# ScanMasterVCI.net
KiCad netlist of a schematic drawn in EAGLE
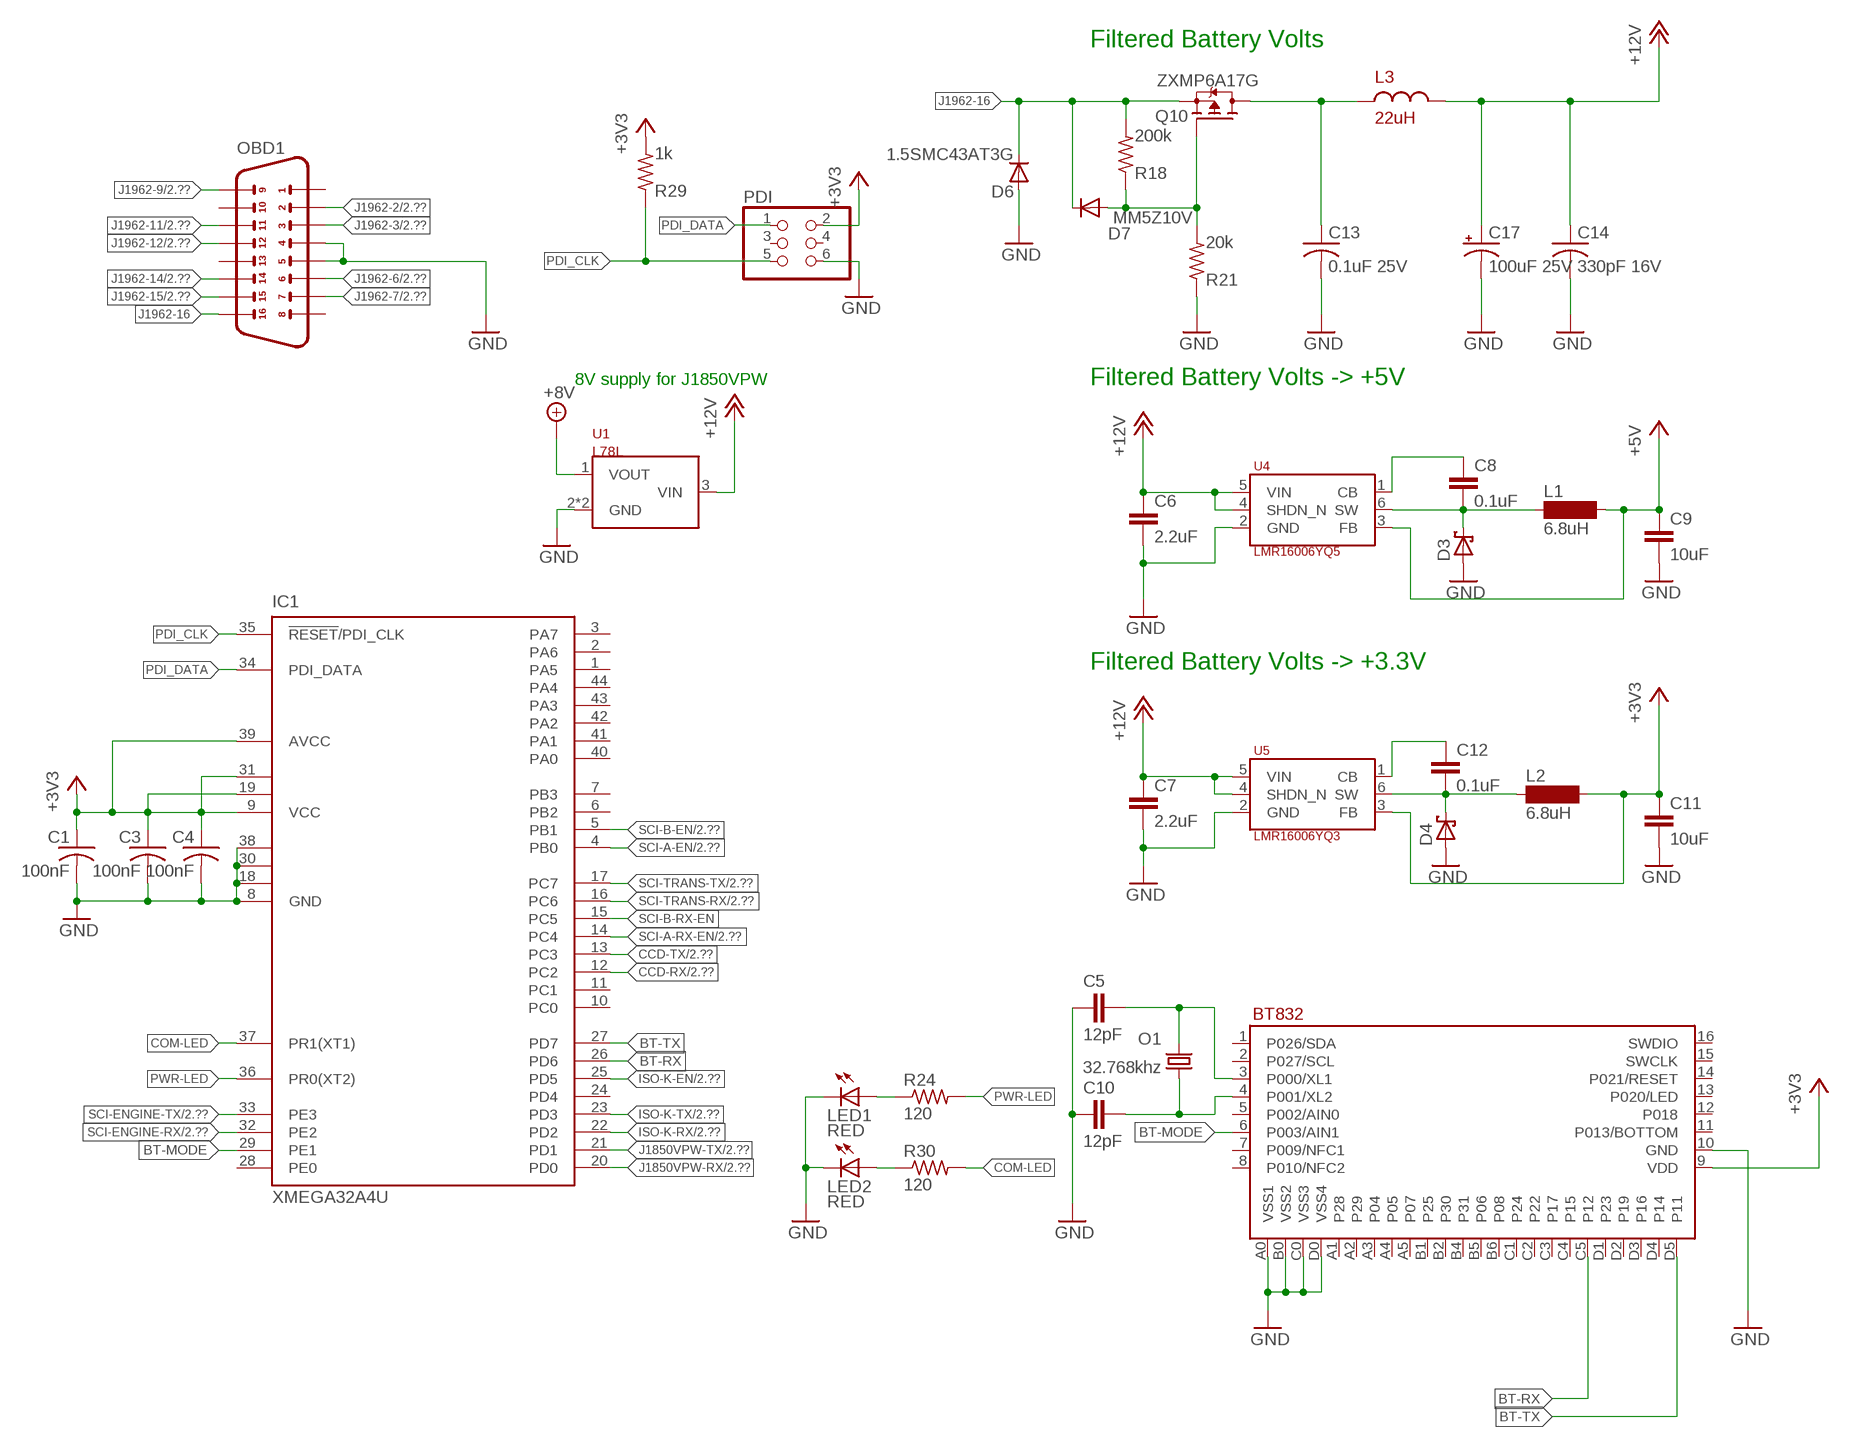
[diagram p0: schematic, sheet 1]
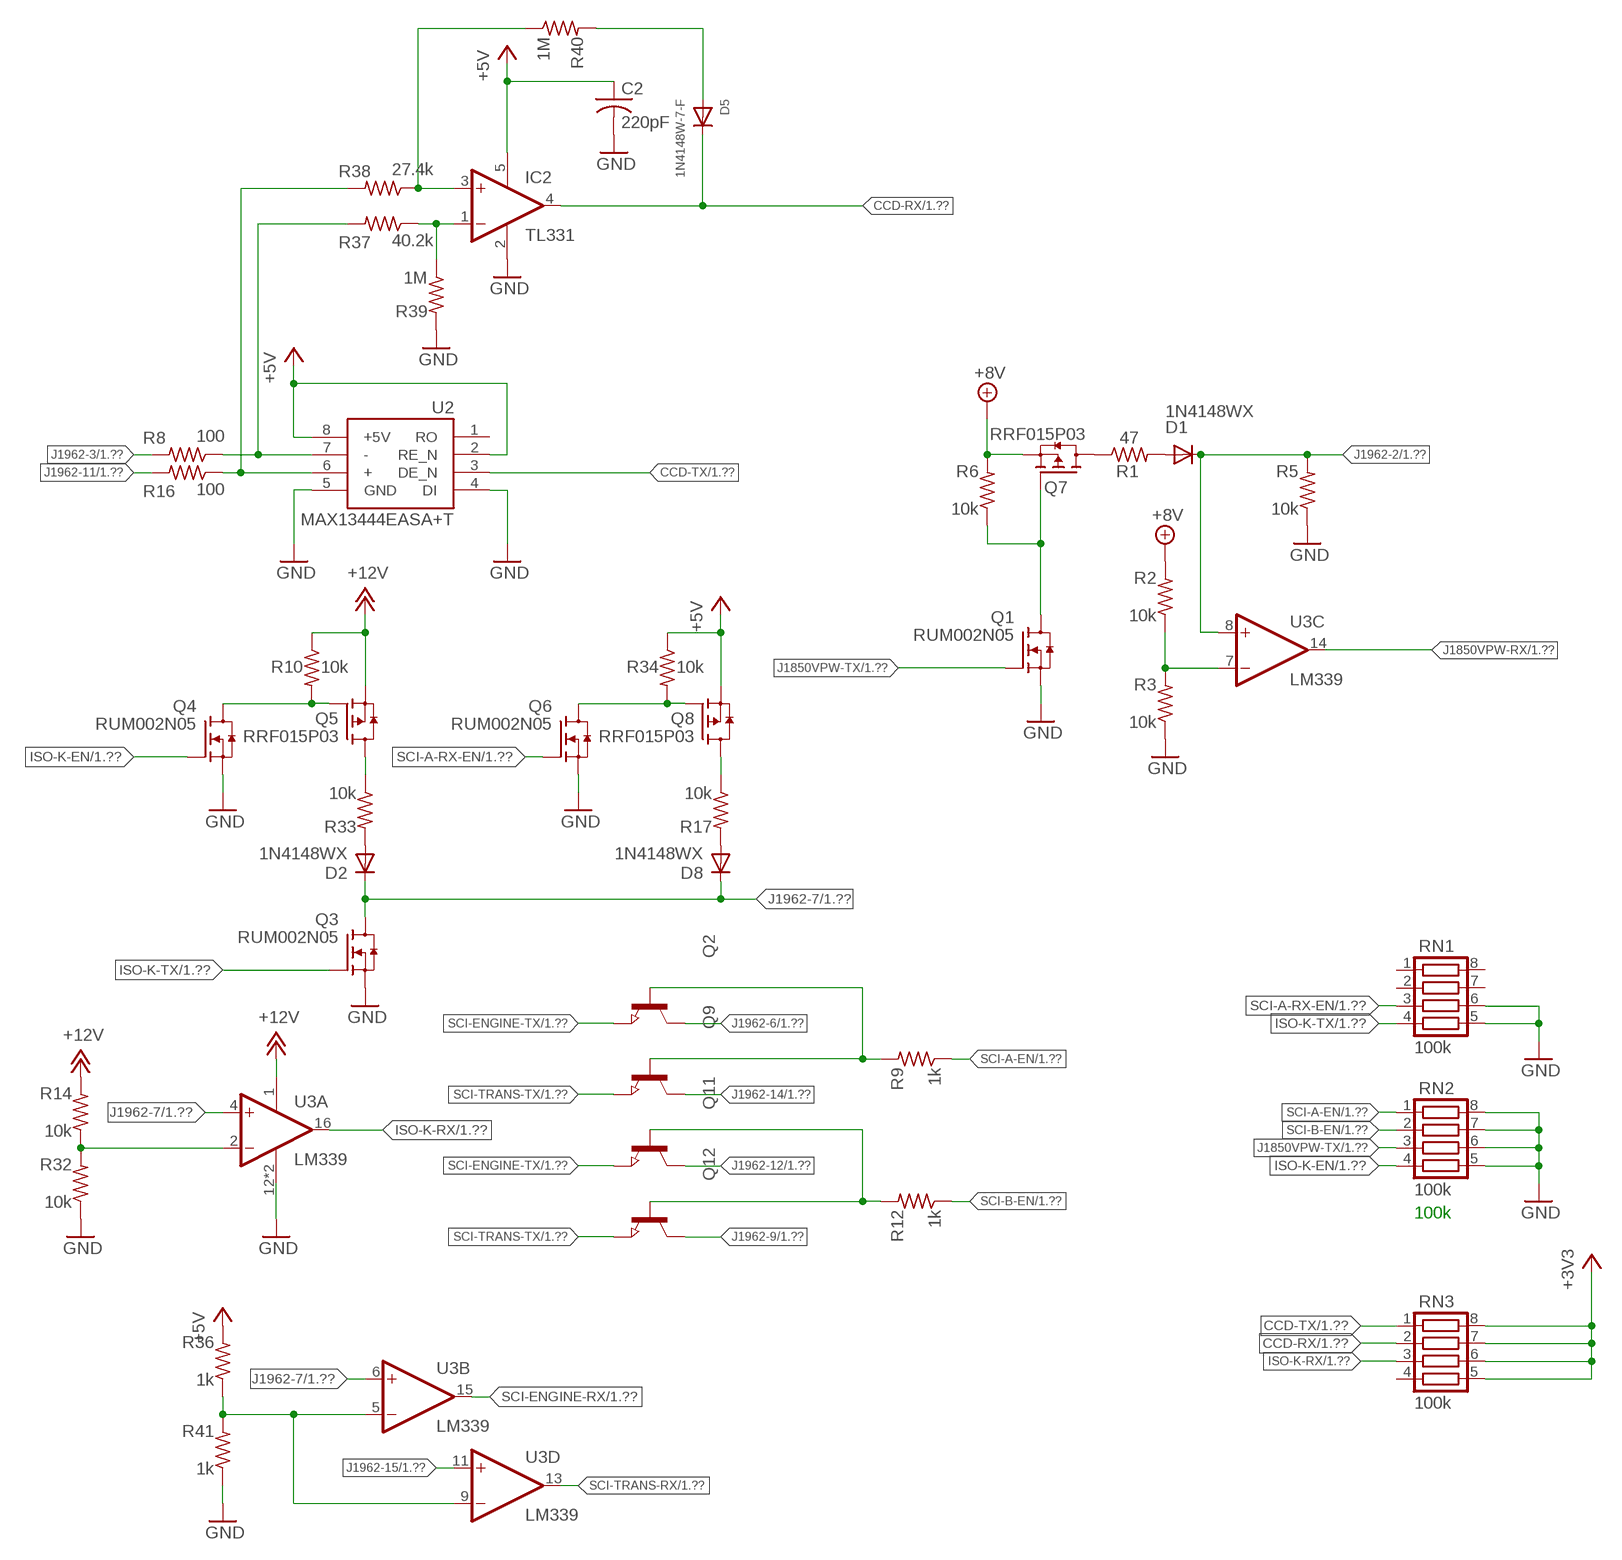
[diagram p1: schematic, sheet 2]

(export (version "E")
  (design (tool "Eeschema 10.0.6"))
  (components
    (comp (ref "C2")
      (value "220pF")
      (footprint "eagle-import:C0603")
      (libsource (lib "eagle-import") (part "C-USC0603"))
    )
    (comp (ref "D1")
      (value "1N4148WX")
      (footprint "eagle-import:SOD323-R")
      (libsource (lib "eagle-import") (part "DIODE-SOD323-R"))
    )
    (comp (ref "D2")
      (value "1N4148WX")
      (footprint "eagle-import:SOD323-R")
      (libsource (lib "eagle-import") (part "DIODE-SOD323-R"))
    )
    (comp (ref "D5")
      (value "1N4148W-7-F")
      (footprint "eagle-import:SOD123FL")
      (libsource (lib "eagle-import") (part "1N4148W-7-F"))
    )
    (comp (ref "D8")
      (value "1N4148WX")
      (footprint "eagle-import:SOD323-R")
      (libsource (lib "eagle-import") (part "DIODE-SOD323-R"))
    )
    (comp (ref "IC2")
      (value "TL331")
      (footprint "eagle-import:DBV-R-PDSO-G5")
      (libsource (lib "eagle-import") (part "TL331"))
    )
    (comp (ref "Q1")
      (value "RUM002N05")
      (footprint "eagle-import:EMT3")
      (libsource (lib "eagle-import") (part "RUM002N05"))
    )
    (comp (ref "Q2")
      (value "NPN-TRANSISTOR_SOT23")
      (footprint "eagle-import:SOT23")
      (libsource (lib "eagle-import") (part "NPN-TRANSISTOR_SOT23"))
    )
    (comp (ref "Q3")
      (value "RUM002N05")
      (footprint "eagle-import:EMT3")
      (libsource (lib "eagle-import") (part "RUM002N05"))
    )
    (comp (ref "Q4")
      (value "RUM002N05")
      (footprint "eagle-import:EMT3")
      (libsource (lib "eagle-import") (part "RUM002N05"))
    )
    (comp (ref "Q5")
      (value "RRF015P03")
      (footprint "eagle-import:SOT323")
      (libsource (lib "eagle-import") (part "RRF015P03"))
    )
    (comp (ref "Q6")
      (value "RUM002N05")
      (footprint "eagle-import:EMT3")
      (libsource (lib "eagle-import") (part "RUM002N05"))
    )
    (comp (ref "Q7")
      (value "RRF015P03")
      (footprint "eagle-import:SOT323")
      (libsource (lib "eagle-import") (part "RRF015P03"))
    )
    (comp (ref "Q8")
      (value "RRF015P03")
      (footprint "eagle-import:SOT323")
      (libsource (lib "eagle-import") (part "RRF015P03"))
    )
    (comp (ref "Q9")
      (value "NPN-TRANSISTOR_SOT23")
      (footprint "eagle-import:SOT23")
      (libsource (lib "eagle-import") (part "NPN-TRANSISTOR_SOT23"))
    )
    (comp (ref "Q11")
      (value "NPN-TRANSISTOR_SOT23")
      (footprint "eagle-import:SOT23")
      (libsource (lib "eagle-import") (part "NPN-TRANSISTOR_SOT23"))
    )
    (comp (ref "Q12")
      (value "NPN-TRANSISTOR_SOT23")
      (footprint "eagle-import:SOT23")
      (libsource (lib "eagle-import") (part "NPN-TRANSISTOR_SOT23"))
    )
    (comp (ref "R1")
      (value "47")
      (footprint "eagle-import:R0603")
      (libsource (lib "eagle-import") (part "R-US_R0603"))
    )
    (comp (ref "R2")
      (value "10k")
      (footprint "eagle-import:R0603")
      (libsource (lib "eagle-import") (part "R-US_R0603"))
    )
    (comp (ref "R3")
      (value "10k")
      (footprint "eagle-import:R0603")
      (libsource (lib "eagle-import") (part "R-US_R0603"))
    )
    (comp (ref "R5")
      (value "10k")
      (footprint "eagle-import:R0603")
      (libsource (lib "eagle-import") (part "R-US_R0603"))
    )
    (comp (ref "R6")
      (value "10k")
      (footprint "eagle-import:R0603")
      (libsource (lib "eagle-import") (part "R-US_R0603"))
    )
    (comp (ref "R8")
      (value "100")
      (footprint "eagle-import:R0603")
      (libsource (lib "eagle-import") (part "R-US_R0603"))
    )
    (comp (ref "R9")
      (value "1k")
      (footprint "eagle-import:R0603")
      (libsource (lib "eagle-import") (part "R-US_R0603"))
    )
    (comp (ref "R10")
      (value "10k")
      (footprint "eagle-import:R0603")
      (libsource (lib "eagle-import") (part "R-US_R0603"))
    )
    (comp (ref "R12")
      (value "1k")
      (footprint "eagle-import:R0603")
      (libsource (lib "eagle-import") (part "R-US_R0603"))
    )
    (comp (ref "R14")
      (value "10k")
      (footprint "eagle-import:R0603")
      (libsource (lib "eagle-import") (part "R-US_R0603"))
    )
    (comp (ref "R16")
      (value "100")
      (footprint "eagle-import:R0603")
      (libsource (lib "eagle-import") (part "R-US_R0603"))
    )
    (comp (ref "R17")
      (value "10k")
      (footprint "eagle-import:R0603")
      (libsource (lib "eagle-import") (part "R-US_R0603"))
    )
    (comp (ref "R32")
      (value "10k")
      (footprint "eagle-import:R0603")
      (libsource (lib "eagle-import") (part "R-US_R0603"))
    )
    (comp (ref "R33")
      (value "10k")
      (footprint "eagle-import:R0603")
      (libsource (lib "eagle-import") (part "R-US_R0603"))
    )
    (comp (ref "R34")
      (value "10k")
      (footprint "eagle-import:R0603")
      (libsource (lib "eagle-import") (part "R-US_R0603"))
    )
    (comp (ref "R36")
      (value "1k")
      (footprint "eagle-import:R0603")
      (libsource (lib "eagle-import") (part "R-US_R0603"))
    )
    (comp (ref "R37")
      (value "40.2k")
      (footprint "eagle-import:R0603")
      (libsource (lib "eagle-import") (part "R-US_R0603"))
    )
    (comp (ref "R38")
      (value "27.4k")
      (footprint "eagle-import:R0603")
      (libsource (lib "eagle-import") (part "R-US_R0603"))
    )
    (comp (ref "R39")
      (value "1M")
      (footprint "eagle-import:R0603")
      (libsource (lib "eagle-import") (part "R-US_R0603"))
    )
    (comp (ref "R40")
      (value "1M")
      (footprint "eagle-import:R0603")
      (libsource (lib "eagle-import") (part "R-US_R0603"))
    )
    (comp (ref "R41")
      (value "1k")
      (footprint "eagle-import:R0603")
      (libsource (lib "eagle-import") (part "R-US_R0603"))
    )
    (comp (ref "RN1")
      (value "100k")
      (footprint "eagle-import:CTS742C083")
      (libsource (lib "eagle-import") (part "CTS742C083"))
    )
    (comp (ref "RN2")
      (value "100k")
      (footprint "eagle-import:CTS742C083")
      (libsource (lib "eagle-import") (part "CTS742C083"))
    )
    (comp (ref "RN3")
      (value "100k")
      (footprint "eagle-import:CTS742C083")
      (libsource (lib "eagle-import") (part "CTS742C083"))
    )
    (comp (ref "U2")
      (value "MAX13444EASA+T")
      (footprint "eagle-import:SO08")
      (libsource (lib "eagle-import") (part "MAX13444EASA+SMD"))
    )
    (comp (ref "U3")
      (value "LM339")
      (footprint "eagle-import:QFN16")
      (libsource (lib "eagle-import") (part "LM339"))
    )
    (comp (ref "C1")
      (value "100nF")
      (footprint "eagle-import:C0402")
      (libsource (lib "eagle-import") (part "C-USC0402"))
    )
    (comp (ref "C3")
      (value "100nF")
      (footprint "eagle-import:C0402")
      (libsource (lib "eagle-import") (part "C-USC0402"))
    )
    (comp (ref "C4")
      (value "100nF")
      (footprint "eagle-import:C0402")
      (libsource (lib "eagle-import") (part "C-USC0402"))
    )
    (comp (ref "C5")
      (value "12pF")
      (footprint "eagle-import:0603")
      (libsource (lib "eagle-import") (part "12PF-0603-50V-5%"))
    )
    (comp (ref "C6")
      (value "2.2uF")
      (footprint "eagle-import:1206")
      (libsource (lib "eagle-import") (part "2.2UF-1206-50V-10%"))
    )
    (comp (ref "C7")
      (value "2.2uF")
      (footprint "eagle-import:1206")
      (libsource (lib "eagle-import") (part "2.2UF-1206-50V-10%"))
    )
    (comp (ref "C8")
      (value "0.1uF")
      (footprint "eagle-import:0603")
      (libsource (lib "eagle-import") (part "0.1UF-0603-25V-(+80/-20%)"))
    )
    (comp (ref "C9")
      (value "10uF")
      (footprint "eagle-import:0603")
      (libsource (lib "eagle-import") (part "10UF-0603-6.3V-20%"))
    )
    (comp (ref "C10")
      (value "12pF")
      (footprint "eagle-import:0603")
      (libsource (lib "eagle-import") (part "12PF-0603-50V-5%"))
    )
    (comp (ref "C11")
      (value "10uF")
      (footprint "eagle-import:0603")
      (libsource (lib "eagle-import") (part "10UF-0603-6.3V-20%"))
    )
    (comp (ref "C12")
      (value "0.1uF")
      (footprint "eagle-import:0603")
      (libsource (lib "eagle-import") (part "0.1UF-0603-25V-(+80/-20%)"))
    )
    (comp (ref "C13")
      (value "0.1uF 25V")
      (footprint "eagle-import:C0603")
      (libsource (lib "eagle-import") (part "C-USC0603"))
    )
    (comp (ref "C14")
      (value "330pF 16V")
      (footprint "eagle-import:C0603")
      (libsource (lib "eagle-import") (part "C-USC0603"))
    )
    (comp (ref "C17")
      (value "100uF 25V")
      (footprint "eagle-import:CPOL-RADIAL-2.5MM-6.5MM")
      (libsource (lib "eagle-import") (part "100UF-POLAR-RADIAL-2.5MM-25V-20%"))
    )
    (comp (ref "D3")
      (value "SM5817PL")
      (footprint "eagle-import:SOD123FL")
      (libsource (lib "eagle-import") (part "SM5817PL"))
    )
    (comp (ref "D4")
      (value "SM5817PL")
      (footprint "eagle-import:SOD123FL")
      (libsource (lib "eagle-import") (part "SM5817PL"))
    )
    (comp (ref "D6")
      (value "1.5SMC43AT3G")
      (footprint "eagle-import:SMC")
      (libsource (lib "eagle-import") (part "DIODE-SMC"))
    )
    (comp (ref "D7")
      (value "MM5Z10V")
      (footprint "eagle-import:SOD523")
      (libsource (lib "eagle-import") (part "DIODE-SOD523"))
    )
    (comp (ref "IC1")
      (value "XMEGA32A4U")
      (footprint "eagle-import:MLF44-TH")
      (libsource (lib "eagle-import") (part "XMEGA16A4M1"))
    )
    (comp (ref "L1")
      (value "6.8uH")
      (footprint "eagle-import:SM-1206")
      (libsource (lib "eagle-import") (part "SM-1206"))
    )
    (comp (ref "L2")
      (value "6.8uH")
      (footprint "eagle-import:SM-1206")
      (libsource (lib "eagle-import") (part "SM-1206"))
    )
    (comp (ref "L3")
      (value "22uH")
      (footprint "eagle-import:L0603")
      (libsource (lib "eagle-import") (part "INDUCTOR"))
    )
    (comp (ref "LED1")
      (value "RED")
      (footprint "eagle-import:CHIP-LED0603")
      (libsource (lib "eagle-import") (part "LEDCHIP-LED0603"))
    )
    (comp (ref "LED2")
      (value "RED")
      (footprint "eagle-import:CHIP-LED0603")
      (libsource (lib "eagle-import") (part "LEDCHIP-LED0603"))
    )
    (comp (ref "O1")
      (value "32.768khz")
      (footprint "eagle-import:FC-135")
      (libsource (lib "eagle-import") (part "SER4103"))
    )
    (comp (ref "OBD1")
      (value "OBD2_OBD2_90")
      (footprint "eagle-import:OBD2")
      (libsource (lib "eagle-import") (part "OBD2_OBD2_90"))
    )
    (comp (ref "PDI")
      (value "PINHD-2X3")
      (footprint "eagle-import:2X03")
      (libsource (lib "eagle-import") (part "PINHD-2X3"))
    )
    (comp (ref "Q10")
      (value "ZXMP6A17G")
      (footprint "eagle-import:SOT223")
      (libsource (lib "eagle-import") (part "ZXMP6A17G"))
    )
    (comp (ref "R18")
      (value "200k")
      (footprint "eagle-import:R0603")
      (libsource (lib "eagle-import") (part "R-US_R0603"))
    )
    (comp (ref "R21")
      (value "20k")
      (footprint "eagle-import:R0603")
      (libsource (lib "eagle-import") (part "R-US_R0603"))
    )
    (comp (ref "R24")
      (value "120")
      (footprint "eagle-import:R0603")
      (libsource (lib "eagle-import") (part "resistor_348_R-US_R0603"))
    )
    (comp (ref "R29")
      (value "1k")
      (footprint "eagle-import:R0603")
      (libsource (lib "eagle-import") (part "R-US_R0603"))
    )
    (comp (ref "R30")
      (value "120")
      (footprint "eagle-import:R0603")
      (libsource (lib "eagle-import") (part "resistor_348_R-US_R0603"))
    )
    (comp (ref "U1")
      (value "L78L")
      (footprint "eagle-import:SOT89")
      (libsource (lib "eagle-import") (part "L78L"))
    )
    (comp (ref "U4")
      (value "LMR16006YQ5")
      (footprint "eagle-import:SOT6")
      (libsource (lib "eagle-import") (part "LMR16006Y"))
    )
    (comp (ref "U5")
      (value "LMR16006YQ3")
      (footprint "eagle-import:SOT6")
      (libsource (lib "eagle-import") (part "LMR16006Y"))
    )
    (comp (ref "U6")
      (value "BT832A")
      (footprint "eagle-import:BT832A")
      (libsource (lib "eagle-import") (part "BT832A"))
    )
  )
  (nets
    (net (code "1") (name "+3V3") (class "Default")
      (node (ref "C1") (pin "1") (pinfunction "1_1") (pintype "passive"))
      (node (ref "C11") (pin "1") (pinfunction "1_1") (pintype "passive"))
      (node (ref "C3") (pin "1") (pinfunction "1_1") (pintype "passive"))
      (node (ref "C4") (pin "1") (pinfunction "1_1") (pintype "passive"))
      (node (ref "IC1") (pin "19") (pinfunction "VCC1_19") (pintype "power_in"))
      (node (ref "IC1") (pin "31") (pinfunction "VCC2_31") (pintype "power_in"))
      (node (ref "IC1") (pin "39") (pinfunction "AVCC_39") (pintype "power_in"))
      (node (ref "IC1") (pin "9") (pinfunction "VCC_9") (pintype "power_in"))
      (node (ref "L2") (pin "2") (pinfunction "2_2") (pintype "passive"))
      (node (ref "PDI") (pin "2") (pinfunction "2_2") (pintype "passive"))
      (node (ref "R29") (pin "2") (pinfunction "2_2") (pintype "passive"))
      (node (ref "RN3") (pin "5") (pinfunction "5_5") (pintype "passive"))
      (node (ref "RN3") (pin "6") (pinfunction "6_6") (pintype "passive"))
      (node (ref "RN3") (pin "7") (pinfunction "7_7") (pintype "passive"))
      (node (ref "RN3") (pin "8") (pinfunction "8_8") (pintype "passive"))
      (node (ref "U5") (pin "3") (pinfunction "FB_3") (pintype "input"))
      (node (ref "U6") (pin "9") (pinfunction "VDD_9") (pintype "bidirectional"))
    )
    (net (code "2") (name "+5V") (class "Default")
      (node (ref "C2") (pin "1") (pinfunction "1_1") (pintype "passive"))
      (node (ref "C9") (pin "1") (pinfunction "1_1") (pintype "passive"))
      (node (ref "IC2") (pin "5") (pinfunction "V+_5") (pintype "power_in"))
      (node (ref "L1") (pin "2") (pinfunction "2_2") (pintype "passive"))
      (node (ref "Q8") (pin "2") (pinfunction "S_2") (pintype "passive"))
      (node (ref "R34") (pin "1") (pinfunction "1_1") (pintype "passive"))
      (node (ref "R36") (pin "2") (pinfunction "2_2") (pintype "passive"))
      (node (ref "U2") (pin "2") (pinfunction "RE_N_2") (pintype "bidirectional"))
      (node (ref "U2") (pin "8") (pinfunction "+5V_8") (pintype "power_in"))
      (node (ref "U4") (pin "3") (pinfunction "FB_3") (pintype "input"))
    )
    (net (code "3") (name "+8V") (class "Default")
      (node (ref "Q7") (pin "2") (pinfunction "S_2") (pintype "passive"))
      (node (ref "R2") (pin "2") (pinfunction "2_2") (pintype "passive"))
      (node (ref "R6") (pin "2") (pinfunction "2_2") (pintype "passive"))
      (node (ref "U1") (pin "1") (pinfunction "VOUT_1") (pintype "power_in"))
    )
    (net (code "4") (name "+12V") (class "Default")
      (node (ref "C14") (pin "1") (pinfunction "1_1") (pintype "passive"))
      (node (ref "C17") (pin "1") (pinfunction "+_1") (pintype "passive"))
      (node (ref "C6") (pin "1") (pinfunction "1_1") (pintype "passive"))
      (node (ref "C7") (pin "1") (pinfunction "1_1") (pintype "passive"))
      (node (ref "L3") (pin "2") (pinfunction "2_2") (pintype "passive"))
      (node (ref "Q5") (pin "2") (pinfunction "S_2") (pintype "passive"))
      (node (ref "R10") (pin "1") (pinfunction "1_1") (pintype "passive"))
      (node (ref "R14") (pin "2") (pinfunction "2_2") (pintype "passive"))
      (node (ref "U1") (pin "3") (pinfunction "VIN_3") (pintype "power_in"))
      (node (ref "U3") (pin "1") (pinfunction "V+_1") (pintype "power_in"))
      (node (ref "U4") (pin "4") (pinfunction "SHDN_N_4") (pintype "input"))
      (node (ref "U4") (pin "5") (pinfunction "VIN_5") (pintype "power_in"))
      (node (ref "U5") (pin "4") (pinfunction "SHDN_N_4") (pintype "input"))
      (node (ref "U5") (pin "5") (pinfunction "VIN_5") (pintype "power_in"))
    )
    (net (code "5") (name "BT-MODE") (class "Default")
      (node (ref "IC1") (pin "29") (pinfunction "PE1_29") (pintype "bidirectional"))
      (node (ref "U6") (pin "6") (pinfunction "P003/AIN1_6") (pintype "bidirectional"))
    )
    (net (code "6") (name "BT-RX") (class "Default")
      (node (ref "IC1") (pin "26") (pinfunction "PD6_26") (pintype "bidirectional"))
      (node (ref "U6") (pin "C5") (pinfunction "P12_C5") (pintype "bidirectional"))
    )
    (net (code "7") (name "BT-TX") (class "Default")
      (node (ref "IC1") (pin "27") (pinfunction "PD7_27") (pintype "bidirectional"))
      (node (ref "U6") (pin "D5") (pinfunction "P11_D5") (pintype "bidirectional"))
    )
    (net (code "8") (name "CCD-RX") (class "Default")
      (node (ref "D5") (pin "C") (pinfunction "C_C") (pintype "passive"))
      (node (ref "IC1") (pin "12") (pinfunction "PC2_12") (pintype "bidirectional"))
      (node (ref "IC2") (pin "4") (pinfunction "OUT_4") (pintype "output"))
      (node (ref "RN3") (pin "2") (pinfunction "2_2") (pintype "passive"))
    )
    (net (code "9") (name "CCD-TX") (class "Default")
      (node (ref "IC1") (pin "13") (pinfunction "PC3_13") (pintype "bidirectional"))
      (node (ref "RN3") (pin "1") (pinfunction "1_1") (pintype "passive"))
      (node (ref "U2") (pin "3") (pinfunction "DE_N_3") (pintype "bidirectional"))
    )
    (net (code "10") (name "COM-LED") (class "Default")
      (node (ref "IC1") (pin "37") (pinfunction "PR1(XT1)_37") (pintype "bidirectional"))
      (node (ref "R30") (pin "2") (pinfunction "2_2") (pintype "passive"))
    )
    (net (code "11") (name "GND") (class "Default")
      (node (ref "C1") (pin "2") (pinfunction "2_2") (pintype "passive"))
      (node (ref "C10") (pin "1") (pinfunction "1_1") (pintype "passive"))
      (node (ref "C11") (pin "2") (pinfunction "2_2") (pintype "passive"))
      (node (ref "C13") (pin "2") (pinfunction "2_2") (pintype "passive"))
      (node (ref "C14") (pin "2") (pinfunction "2_2") (pintype "passive"))
      (node (ref "C17") (pin "2") (pinfunction "-_2") (pintype "passive"))
      (node (ref "C2") (pin "2") (pinfunction "2_2") (pintype "passive"))
      (node (ref "C3") (pin "2") (pinfunction "2_2") (pintype "passive"))
      (node (ref "C4") (pin "2") (pinfunction "2_2") (pintype "passive"))
      (node (ref "C5") (pin "1") (pinfunction "1_1") (pintype "passive"))
      (node (ref "C6") (pin "2") (pinfunction "2_2") (pintype "passive"))
      (node (ref "C7") (pin "2") (pinfunction "2_2") (pintype "passive"))
      (node (ref "C9") (pin "2") (pinfunction "2_2") (pintype "passive"))
      (node (ref "D3") (pin "A") (pinfunction "A_A") (pintype "passive"))
      (node (ref "D4") (pin "A") (pinfunction "A_A") (pintype "passive"))
      (node (ref "D6") (pin "A") (pinfunction "A_A") (pintype "passive"))
      (node (ref "IC1") (pin "18") (pinfunction "GND1_18") (pintype "power_in"))
      (node (ref "IC1") (pin "30") (pinfunction "GND2_30") (pintype "power_in"))
      (node (ref "IC1") (pin "38") (pinfunction "GND3_38") (pintype "power_in"))
      (node (ref "IC1") (pin "8") (pinfunction "GND_8") (pintype "power_in"))
      (node (ref "IC2") (pin "2") (pinfunction "GND_2") (pintype "power_in"))
      (node (ref "LED1") (pin "C") (pinfunction "C_C") (pintype "passive"))
      (node (ref "LED2") (pin "C") (pinfunction "C_C") (pintype "passive"))
      (node (ref "OBD1") (pin "4") (pinfunction "4_4") (pintype "bidirectional"))
      (node (ref "OBD1") (pin "5") (pinfunction "5_5") (pintype "bidirectional"))
      (node (ref "PDI") (pin "6") (pinfunction "6_6") (pintype "passive"))
      (node (ref "Q1") (pin "2") (pinfunction "S_2") (pintype "passive"))
      (node (ref "Q3") (pin "2") (pinfunction "S_2") (pintype "passive"))
      (node (ref "Q4") (pin "2") (pinfunction "S_2") (pintype "passive"))
      (node (ref "Q6") (pin "2") (pinfunction "S_2") (pintype "passive"))
      (node (ref "R21") (pin "1") (pinfunction "1_1") (pintype "passive"))
      (node (ref "R3") (pin "1") (pinfunction "1_1") (pintype "passive"))
      (node (ref "R32") (pin "1") (pinfunction "1_1") (pintype "passive"))
      (node (ref "R39") (pin "2") (pinfunction "2_2") (pintype "passive"))
      (node (ref "R41") (pin "1") (pinfunction "1_1") (pintype "passive"))
      (node (ref "R5") (pin "1") (pinfunction "1_1") (pintype "passive"))
      (node (ref "RN1") (pin "5") (pinfunction "5_5") (pintype "passive"))
      (node (ref "RN1") (pin "6") (pinfunction "6_6") (pintype "passive"))
      (node (ref "RN2") (pin "5") (pinfunction "5_5") (pintype "passive"))
      (node (ref "RN2") (pin "6") (pinfunction "6_6") (pintype "passive"))
      (node (ref "RN2") (pin "7") (pinfunction "7_7") (pintype "passive"))
      (node (ref "RN2") (pin "8") (pinfunction "8_8") (pintype "passive"))
      (node (ref "U1") (pin "2") (pinfunction "GND_2") (pintype "power_in"))
      (node (ref "U1") (pin "2@1") (pinfunction "GND_2@1") (pintype "power_in"))
      (node (ref "U2") (pin "4") (pinfunction "DI_4") (pintype "power_in"))
      (node (ref "U2") (pin "5") (pinfunction "GND_5") (pintype "bidirectional"))
      (node (ref "U3") (pin "12") (pinfunction "V-_12") (pintype "power_in"))
      (node (ref "U3") (pin "PAD") (pinfunction "V-_PAD") (pintype "power_in"))
      (node (ref "U4") (pin "2") (pinfunction "GND_2") (pintype "power_in"))
      (node (ref "U5") (pin "2") (pinfunction "GND_2") (pintype "power_in"))
      (node (ref "U6") (pin "10") (pinfunction "GND_10") (pintype "bidirectional"))
      (node (ref "U6") (pin "A0") (pinfunction "VSS1_A0") (pintype "bidirectional"))
      (node (ref "U6") (pin "B0") (pinfunction "VSS2_B0") (pintype "bidirectional"))
      (node (ref "U6") (pin "C0") (pinfunction "VSS3_C0") (pintype "bidirectional"))
      (node (ref "U6") (pin "D0") (pinfunction "VSS4_D0") (pintype "bidirectional"))
    )
    (net (code "12") (name "ISO-K-EN") (class "Default")
      (node (ref "IC1") (pin "25") (pinfunction "PD5_25") (pintype "bidirectional"))
      (node (ref "Q4") (pin "1") (pinfunction "G_1") (pintype "passive"))
      (node (ref "RN2") (pin "4") (pinfunction "4_4") (pintype "passive"))
    )
    (net (code "13") (name "ISO-K-RX") (class "Default")
      (node (ref "IC1") (pin "22") (pinfunction "PD2_22") (pintype "bidirectional"))
      (node (ref "RN3") (pin "3") (pinfunction "3_3") (pintype "passive"))
      (node (ref "U3") (pin "16") (pinfunction "OUT_16") (pintype "output"))
    )
    (net (code "14") (name "ISO-K-TX") (class "Default")
      (node (ref "IC1") (pin "23") (pinfunction "PD3_23") (pintype "bidirectional"))
      (node (ref "Q3") (pin "1") (pinfunction "G_1") (pintype "passive"))
      (node (ref "RN1") (pin "4") (pinfunction "4_4") (pintype "passive"))
    )
    (net (code "15") (name "J1850VPW-RX") (class "Default")
      (node (ref "IC1") (pin "20") (pinfunction "PD0_20") (pintype "bidirectional"))
      (node (ref "U3") (pin "14") (pinfunction "OUT_14") (pintype "output"))
    )
    (net (code "16") (name "J1850VPW-TX") (class "Default")
      (node (ref "IC1") (pin "21") (pinfunction "PD1_21") (pintype "bidirectional"))
      (node (ref "Q1") (pin "1") (pinfunction "G_1") (pintype "passive"))
      (node (ref "RN2") (pin "3") (pinfunction "3_3") (pintype "passive"))
    )
    (net (code "17") (name "J1962-2") (class "Default")
      (node (ref "D1") (pin "C") (pinfunction "C_C") (pintype "passive"))
      (node (ref "OBD1") (pin "2") (pinfunction "2_2") (pintype "bidirectional"))
      (node (ref "R5") (pin "2") (pinfunction "2_2") (pintype "passive"))
      (node (ref "U3") (pin "8") (pinfunction "+IN_8") (pintype "input"))
    )
    (net (code "18") (name "J1962-3") (class "Default")
      (node (ref "OBD1") (pin "3") (pinfunction "3_3") (pintype "bidirectional"))
      (node (ref "R8") (pin "2") (pinfunction "2_2") (pintype "passive"))
    )
    (net (code "19") (name "J1962-6") (class "Default")
      (node (ref "OBD1") (pin "6") (pinfunction "6_6") (pintype "bidirectional"))
      (node (ref "Q2") (pin "3") (pinfunction "C_3") (pintype "passive"))
    )
    (net (code "20") (name "J1962-7") (class "Default")
      (node (ref "D2") (pin "C") (pinfunction "C_C") (pintype "passive"))
      (node (ref "D8") (pin "C") (pinfunction "C_C") (pintype "passive"))
      (node (ref "OBD1") (pin "7") (pinfunction "7_7") (pintype "bidirectional"))
      (node (ref "Q3") (pin "3") (pinfunction "D_3") (pintype "passive"))
      (node (ref "U3") (pin "4") (pinfunction "+IN_4") (pintype "input"))
      (node (ref "U3") (pin "6") (pinfunction "+IN_6") (pintype "input"))
    )
    (net (code "21") (name "J1962-9") (class "Default")
      (node (ref "OBD1") (pin "9") (pinfunction "9_9") (pintype "bidirectional"))
      (node (ref "Q12") (pin "3") (pinfunction "C_3") (pintype "passive"))
    )
    (net (code "22") (name "J1962-11") (class "Default")
      (node (ref "OBD1") (pin "11") (pinfunction "11_11") (pintype "bidirectional"))
      (node (ref "R16") (pin "2") (pinfunction "2_2") (pintype "passive"))
    )
    (net (code "23") (name "J1962-12") (class "Default")
      (node (ref "OBD1") (pin "12") (pinfunction "12_12") (pintype "bidirectional"))
      (node (ref "Q11") (pin "3") (pinfunction "C_3") (pintype "passive"))
    )
    (net (code "24") (name "J1962-14") (class "Default")
      (node (ref "OBD1") (pin "14") (pinfunction "14_14") (pintype "bidirectional"))
      (node (ref "Q9") (pin "3") (pinfunction "C_3") (pintype "passive"))
    )
    (net (code "25") (name "J1962-15") (class "Default")
      (node (ref "OBD1") (pin "15") (pinfunction "15_15") (pintype "bidirectional"))
      (node (ref "U3") (pin "11") (pinfunction "+IN_11") (pintype "input"))
    )
    (net (code "26") (name "J1962-16") (class "Default")
      (node (ref "D6") (pin "C") (pinfunction "C_C") (pintype "passive"))
      (node (ref "D7") (pin "C") (pinfunction "C_C") (pintype "passive"))
      (node (ref "OBD1") (pin "16") (pinfunction "16_16") (pintype "bidirectional"))
      (node (ref "Q10") (pin "3") (pinfunction "S_3") (pintype "passive"))
      (node (ref "R18") (pin "2") (pinfunction "2_2") (pintype "passive"))
    )
    (net (code "27") (name "Net-(C13-Pad1)") (class "Default")
      (node (ref "C13") (pin "1") (pinfunction "1_1") (pintype "passive"))
      (node (ref "L3") (pin "1") (pinfunction "1_1") (pintype "passive"))
      (node (ref "Q10") (pin "2") (pinfunction "D_2") (pintype "passive"))
      (node (ref "Q10") (pin "4") (pinfunction "D_4") (pintype "passive"))
    )
    (net (code "28") (name "Net-(D1-PadA)") (class "Default")
      (node (ref "D1") (pin "A") (pinfunction "A_A") (pintype "passive"))
      (node (ref "R1") (pin "2") (pinfunction "2_2") (pintype "passive"))
    )
    (net (code "29") (name "Net-(D2-PadA)") (class "Default")
      (node (ref "D2") (pin "A") (pinfunction "A_A") (pintype "passive"))
      (node (ref "R33") (pin "2") (pinfunction "2_2") (pintype "passive"))
    )
    (net (code "30") (name "Net-(D5-PadA)") (class "Default")
      (node (ref "D5") (pin "A") (pinfunction "A_A") (pintype "passive"))
      (node (ref "R40") (pin "2") (pinfunction "2_2") (pintype "passive"))
    )
    (net (code "31") (name "Net-(D8-PadA)") (class "Default")
      (node (ref "D8") (pin "A") (pinfunction "A_A") (pintype "passive"))
      (node (ref "R17") (pin "2") (pinfunction "2_2") (pintype "passive"))
    )
    (net (code "32") (name "Net-(IC2-+IN)") (class "Default")
      (node (ref "IC2") (pin "3") (pinfunction "+IN_3") (pintype "input"))
      (node (ref "R38") (pin "1") (pinfunction "1_1") (pintype "passive"))
      (node (ref "R40") (pin "1") (pinfunction "1_1") (pintype "passive"))
    )
    (net (code "33") (name "Net-(IC2--IN)") (class "Default")
      (node (ref "IC2") (pin "1") (pinfunction "-IN_1") (pintype "input"))
      (node (ref "R37") (pin "1") (pinfunction "1_1") (pintype "passive"))
      (node (ref "R39") (pin "1") (pinfunction "1_1") (pintype "passive"))
    )
    (net (code "34") (name "Net-(LED1-PadA)") (class "Default")
      (node (ref "LED1") (pin "A") (pinfunction "A_A") (pintype "passive"))
      (node (ref "R24") (pin "1") (pinfunction "1_1") (pintype "passive"))
    )
    (net (code "35") (name "Net-(LED2-PadA)") (class "Default")
      (node (ref "LED2") (pin "A") (pinfunction "A_A") (pintype "passive"))
      (node (ref "R30") (pin "1") (pinfunction "1_1") (pintype "passive"))
    )
    (net (code "36") (name "Net-(Q1-D)") (class "Default")
      (node (ref "Q1") (pin "3") (pinfunction "D_3") (pintype "passive"))
      (node (ref "Q7") (pin "1") (pinfunction "G_1") (pintype "passive"))
      (node (ref "R6") (pin "1") (pinfunction "1_1") (pintype "passive"))
    )
    (net (code "37") (name "Net-(Q2-B)") (class "Default")
      (node (ref "Q2") (pin "1") (pinfunction "B_1") (pintype "passive"))
      (node (ref "Q9") (pin "1") (pinfunction "B_1") (pintype "passive"))
      (node (ref "R9") (pin "2") (pinfunction "2_2") (pintype "passive"))
    )
    (net (code "38") (name "Net-(Q4-D)") (class "Default")
      (node (ref "Q4") (pin "3") (pinfunction "D_3") (pintype "passive"))
      (node (ref "Q5") (pin "1") (pinfunction "G_1") (pintype "passive"))
      (node (ref "R10") (pin "2") (pinfunction "2_2") (pintype "passive"))
    )
    (net (code "39") (name "Net-(Q5-D)") (class "Default")
      (node (ref "Q5") (pin "3") (pinfunction "D_3") (pintype "passive"))
      (node (ref "R33") (pin "1") (pinfunction "1_1") (pintype "passive"))
    )
    (net (code "40") (name "Net-(Q6-D)") (class "Default")
      (node (ref "Q6") (pin "3") (pinfunction "D_3") (pintype "passive"))
      (node (ref "Q8") (pin "1") (pinfunction "G_1") (pintype "passive"))
      (node (ref "R34") (pin "2") (pinfunction "2_2") (pintype "passive"))
    )
    (net (code "41") (name "Net-(Q7-D)") (class "Default")
      (node (ref "Q7") (pin "3") (pinfunction "D_3") (pintype "passive"))
      (node (ref "R1") (pin "1") (pinfunction "1_1") (pintype "passive"))
    )
    (net (code "42") (name "Net-(Q8-D)") (class "Default")
      (node (ref "Q8") (pin "3") (pinfunction "D_3") (pintype "passive"))
      (node (ref "R17") (pin "1") (pinfunction "1_1") (pintype "passive"))
    )
    (net (code "43") (name "Net-(Q10-G)") (class "Default")
      (node (ref "D7") (pin "A") (pinfunction "A_A") (pintype "passive"))
      (node (ref "Q10") (pin "1") (pinfunction "G_1") (pintype "passive"))
      (node (ref "R18") (pin "1") (pinfunction "1_1") (pintype "passive"))
      (node (ref "R21") (pin "2") (pinfunction "2_2") (pintype "passive"))
    )
    (net (code "44") (name "Net-(Q11-B)") (class "Default")
      (node (ref "Q11") (pin "1") (pinfunction "B_1") (pintype "passive"))
      (node (ref "Q12") (pin "1") (pinfunction "B_1") (pintype "passive"))
      (node (ref "R12") (pin "2") (pinfunction "2_2") (pintype "passive"))
    )
    (net (code "45") (name "Net-(U2-+)") (class "Default")
      (node (ref "R16") (pin "1") (pinfunction "1_1") (pintype "passive"))
      (node (ref "R38") (pin "2") (pinfunction "2_2") (pintype "passive"))
      (node (ref "U2") (pin "6") (pinfunction "+_6") (pintype "bidirectional"))
    )
    (net (code "46") (name "Net-(U2--)") (class "Default")
      (node (ref "R37") (pin "2") (pinfunction "2_2") (pintype "passive"))
      (node (ref "R8") (pin "1") (pinfunction "1_1") (pintype "passive"))
      (node (ref "U2") (pin "7") (pinfunction "-_7") (pintype "bidirectional"))
    )
    (net (code "47") (name "Net-(U3A--IN)") (class "Default")
      (node (ref "R14") (pin "1") (pinfunction "1_1") (pintype "passive"))
      (node (ref "R32") (pin "2") (pinfunction "2_2") (pintype "passive"))
      (node (ref "U3") (pin "2") (pinfunction "-IN_2") (pintype "input"))
    )
    (net (code "48") (name "Net-(U3B--IN)") (class "Default")
      (node (ref "R36") (pin "1") (pinfunction "1_1") (pintype "passive"))
      (node (ref "R41") (pin "2") (pinfunction "2_2") (pintype "passive"))
      (node (ref "U3") (pin "5") (pinfunction "-IN_5") (pintype "input"))
      (node (ref "U3") (pin "9") (pinfunction "-IN_9") (pintype "input"))
    )
    (net (code "49") (name "Net-(U3C--IN)") (class "Default")
      (node (ref "R2") (pin "1") (pinfunction "1_1") (pintype "passive"))
      (node (ref "R3") (pin "2") (pinfunction "2_2") (pintype "passive"))
      (node (ref "U3") (pin "7") (pinfunction "-IN_7") (pintype "input"))
    )
    (net (code "50") (name "Net-(U4-CB)") (class "Default")
      (node (ref "C8") (pin "1") (pinfunction "1_1") (pintype "passive"))
      (node (ref "U4") (pin "1") (pinfunction "CB_1") (pintype "input"))
    )
    (net (code "51") (name "Net-(U4-SW)") (class "Default")
      (node (ref "C8") (pin "2") (pinfunction "2_2") (pintype "passive"))
      (node (ref "D3") (pin "C") (pinfunction "C_C") (pintype "passive"))
      (node (ref "L1") (pin "1") (pinfunction "1_1") (pintype "passive"))
      (node (ref "U4") (pin "6") (pinfunction "SW_6") (pintype "output"))
    )
    (net (code "52") (name "Net-(U5-CB)") (class "Default")
      (node (ref "C12") (pin "1") (pinfunction "1_1") (pintype "passive"))
      (node (ref "U5") (pin "1") (pinfunction "CB_1") (pintype "input"))
    )
    (net (code "53") (name "Net-(U5-SW)") (class "Default")
      (node (ref "C12") (pin "2") (pinfunction "2_2") (pintype "passive"))
      (node (ref "D4") (pin "C") (pinfunction "C_C") (pintype "passive"))
      (node (ref "L2") (pin "1") (pinfunction "1_1") (pintype "passive"))
      (node (ref "U5") (pin "6") (pinfunction "SW_6") (pintype "output"))
    )
    (net (code "54") (name "Net-(U6-P000{slash}XL1)") (class "Default")
      (node (ref "C5") (pin "2") (pinfunction "2_2") (pintype "passive"))
      (node (ref "O1") (pin "2") (pinfunction "2_2") (pintype "passive"))
      (node (ref "U6") (pin "3") (pinfunction "P000/XL1_3") (pintype "bidirectional"))
    )
    (net (code "55") (name "Net-(U6-P001{slash}XL2)") (class "Default")
      (node (ref "C10") (pin "2") (pinfunction "2_2") (pintype "passive"))
      (node (ref "O1") (pin "1") (pinfunction "1_1") (pintype "passive"))
      (node (ref "U6") (pin "4") (pinfunction "P001/XL2_4") (pintype "bidirectional"))
    )
    (net (code "56") (name "PDI_CLK") (class "Default")
      (node (ref "IC1") (pin "35") (pinfunction "~{RESET}/PDI_CLK_35") (pintype "bidirectional"))
      (node (ref "PDI") (pin "5") (pinfunction "5_5") (pintype "passive"))
      (node (ref "R29") (pin "1") (pinfunction "1_1") (pintype "passive"))
    )
    (net (code "57") (name "PDI_DATA") (class "Default")
      (node (ref "IC1") (pin "34") (pinfunction "PDI_DATA_34") (pintype "bidirectional"))
      (node (ref "PDI") (pin "1") (pinfunction "1_1") (pintype "passive"))
    )
    (net (code "58") (name "PWR-LED") (class "Default")
      (node (ref "IC1") (pin "36") (pinfunction "PR0(XT2)_36") (pintype "bidirectional"))
      (node (ref "R24") (pin "2") (pinfunction "2_2") (pintype "passive"))
    )
    (net (code "59") (name "SCI-A-EN") (class "Default")
      (node (ref "IC1") (pin "4") (pinfunction "PB0_4") (pintype "bidirectional"))
      (node (ref "R9") (pin "1") (pinfunction "1_1") (pintype "passive"))
      (node (ref "RN2") (pin "1") (pinfunction "1_1") (pintype "passive"))
    )
    (net (code "60") (name "SCI-A-RX-EN") (class "Default")
      (node (ref "IC1") (pin "14") (pinfunction "PC4_14") (pintype "bidirectional"))
      (node (ref "Q6") (pin "1") (pinfunction "G_1") (pintype "passive"))
      (node (ref "RN1") (pin "3") (pinfunction "3_3") (pintype "passive"))
    )
    (net (code "61") (name "SCI-B-EN") (class "Default")
      (node (ref "IC1") (pin "5") (pinfunction "PB1_5") (pintype "bidirectional"))
      (node (ref "R12") (pin "1") (pinfunction "1_1") (pintype "passive"))
      (node (ref "RN2") (pin "2") (pinfunction "2_2") (pintype "passive"))
    )
    (net (code "62") (name "SCI-B-RX-EN") (class "Default")
      (node (ref "IC1") (pin "15") (pinfunction "PC5_15") (pintype "bidirectional"))
    )
    (net (code "63") (name "SCI-ENGINE-RX") (class "Default")
      (node (ref "IC1") (pin "32") (pinfunction "PE2_32") (pintype "bidirectional"))
      (node (ref "U3") (pin "15") (pinfunction "OUT_15") (pintype "output"))
    )
    (net (code "64") (name "SCI-ENGINE-TX") (class "Default")
      (node (ref "IC1") (pin "33") (pinfunction "PE3_33") (pintype "bidirectional"))
      (node (ref "Q11") (pin "2") (pinfunction "E_2") (pintype "passive"))
      (node (ref "Q2") (pin "2") (pinfunction "E_2") (pintype "passive"))
    )
    (net (code "65") (name "SCI-TRANS-RX") (class "Default")
      (node (ref "IC1") (pin "16") (pinfunction "PC6_16") (pintype "bidirectional"))
      (node (ref "U3") (pin "13") (pinfunction "OUT_13") (pintype "output"))
    )
    (net (code "66") (name "SCI-TRANS-TX") (class "Default")
      (node (ref "IC1") (pin "17") (pinfunction "PC7_17") (pintype "bidirectional"))
      (node (ref "Q12") (pin "2") (pinfunction "E_2") (pintype "passive"))
      (node (ref "Q9") (pin "2") (pinfunction "E_2") (pintype "passive"))
    )
    (net (code "67") (name "unconnected-(IC1-PA0-Pad40)") (class "Default")
      (node (ref "IC1") (pin "40") (pinfunction "PA0_40") (pintype "bidirectional"))
    )
    (net (code "68") (name "unconnected-(IC1-PA1-Pad41)") (class "Default")
      (node (ref "IC1") (pin "41") (pinfunction "PA1_41") (pintype "bidirectional"))
    )
    (net (code "69") (name "unconnected-(IC1-PA2-Pad42)") (class "Default")
      (node (ref "IC1") (pin "42") (pinfunction "PA2_42") (pintype "bidirectional"))
    )
    (net (code "70") (name "unconnected-(IC1-PA3-Pad43)") (class "Default")
      (node (ref "IC1") (pin "43") (pinfunction "PA3_43") (pintype "bidirectional"))
    )
    (net (code "71") (name "unconnected-(IC1-PA4-Pad44)") (class "Default")
      (node (ref "IC1") (pin "44") (pinfunction "PA4_44") (pintype "bidirectional"))
    )
    (net (code "72") (name "unconnected-(IC1-PA5-Pad1)") (class "Default")
      (node (ref "IC1") (pin "1") (pinfunction "PA5_1") (pintype "bidirectional"))
    )
    (net (code "73") (name "unconnected-(IC1-PA6-Pad2)") (class "Default")
      (node (ref "IC1") (pin "2") (pinfunction "PA6_2") (pintype "bidirectional"))
    )
    (net (code "74") (name "unconnected-(IC1-PA7-Pad3)") (class "Default")
      (node (ref "IC1") (pin "3") (pinfunction "PA7_3") (pintype "bidirectional"))
    )
    (net (code "75") (name "unconnected-(IC1-PB2-Pad6)") (class "Default")
      (node (ref "IC1") (pin "6") (pinfunction "PB2_6") (pintype "bidirectional"))
    )
    (net (code "76") (name "unconnected-(IC1-PB3-Pad7)") (class "Default")
      (node (ref "IC1") (pin "7") (pinfunction "PB3_7") (pintype "bidirectional"))
    )
    (net (code "77") (name "unconnected-(IC1-PC0-Pad10)") (class "Default")
      (node (ref "IC1") (pin "10") (pinfunction "PC0_10") (pintype "bidirectional"))
    )
    (net (code "78") (name "unconnected-(IC1-PC1-Pad11)") (class "Default")
      (node (ref "IC1") (pin "11") (pinfunction "PC1_11") (pintype "bidirectional"))
    )
    (net (code "79") (name "unconnected-(IC1-PD4-Pad24)") (class "Default")
      (node (ref "IC1") (pin "24") (pinfunction "PD4_24") (pintype "bidirectional"))
    )
    (net (code "80") (name "unconnected-(IC1-PE0-Pad28)") (class "Default")
      (node (ref "IC1") (pin "28") (pinfunction "PE0_28") (pintype "bidirectional"))
    )
    (net (code "81") (name "unconnected-(OBD1-Pad1)") (class "Default")
      (node (ref "OBD1") (pin "1") (pinfunction "1_1") (pintype "bidirectional"))
    )
    (net (code "82") (name "unconnected-(OBD1-Pad8)") (class "Default")
      (node (ref "OBD1") (pin "8") (pinfunction "8_8") (pintype "bidirectional"))
    )
    (net (code "83") (name "unconnected-(OBD1-Pad10)") (class "Default")
      (node (ref "OBD1") (pin "10") (pinfunction "10_10") (pintype "bidirectional"))
    )
    (net (code "84") (name "unconnected-(OBD1-Pad13)") (class "Default")
      (node (ref "OBD1") (pin "13") (pinfunction "13_13") (pintype "bidirectional"))
    )
    (net (code "85") (name "unconnected-(PDI-Pad3)") (class "Default")
      (node (ref "PDI") (pin "3") (pinfunction "3_3") (pintype "passive"))
    )
    (net (code "86") (name "unconnected-(PDI-Pad4)") (class "Default")
      (node (ref "PDI") (pin "4") (pinfunction "4_4") (pintype "passive"))
    )
    (net (code "87") (name "unconnected-(RN1-Pad1)") (class "Default")
      (node (ref "RN1") (pin "1") (pinfunction "1_1") (pintype "passive"))
    )
    (net (code "88") (name "unconnected-(RN1-Pad2)") (class "Default")
      (node (ref "RN1") (pin "2") (pinfunction "2_2") (pintype "passive"))
    )
    (net (code "89") (name "unconnected-(RN1-Pad7)") (class "Default")
      (node (ref "RN1") (pin "7") (pinfunction "7_7") (pintype "passive"))
    )
    (net (code "90") (name "unconnected-(RN1-Pad8)") (class "Default")
      (node (ref "RN1") (pin "8") (pinfunction "8_8") (pintype "passive"))
    )
    (net (code "91") (name "unconnected-(RN3-Pad4)") (class "Default")
      (node (ref "RN3") (pin "4") (pinfunction "4_4") (pintype "passive"))
    )
    (net (code "92") (name "unconnected-(U2-RO-Pad1)") (class "Default")
      (node (ref "U2") (pin "1") (pinfunction "RO_1") (pintype "bidirectional"))
    )
    (net (code "93") (name "unconnected-(U6-P002{slash}AIN0-Pad5)") (class "Default")
      (node (ref "U6") (pin "5") (pinfunction "P002/AIN0_5") (pintype "bidirectional"))
    )
    (net (code "94") (name "unconnected-(U6-P04-PadA3)") (class "Default")
      (node (ref "U6") (pin "A3") (pinfunction "P04_A3") (pintype "bidirectional"))
    )
    (net (code "95") (name "unconnected-(U6-P05-PadA4)") (class "Default")
      (node (ref "U6") (pin "A4") (pinfunction "P05_A4") (pintype "bidirectional"))
    )
    (net (code "96") (name "unconnected-(U6-P06-PadB5)") (class "Default")
      (node (ref "U6") (pin "B5") (pinfunction "P06_B5") (pintype "bidirectional"))
    )
    (net (code "97") (name "unconnected-(U6-P07-PadA5)") (class "Default")
      (node (ref "U6") (pin "A5") (pinfunction "P07_A5") (pintype "bidirectional"))
    )
    (net (code "98") (name "unconnected-(U6-P08-PadB6)") (class "Default")
      (node (ref "U6") (pin "B6") (pinfunction "P08_B6") (pintype "bidirectional"))
    )
    (net (code "99") (name "unconnected-(U6-P009{slash}NFC1-Pad7)") (class "Default")
      (node (ref "U6") (pin "7") (pinfunction "P009/NFC1_7") (pintype "bidirectional"))
    )
    (net (code "100") (name "unconnected-(U6-P010{slash}NFC2-Pad8)") (class "Default")
      (node (ref "U6") (pin "8") (pinfunction "P010/NFC2_8") (pintype "bidirectional"))
    )
    (net (code "101") (name "unconnected-(U6-P013{slash}BOTTOM-Pad11)") (class "Default")
      (node (ref "U6") (pin "11") (pinfunction "P013/BOTTOM_11") (pintype "bidirectional"))
    )
    (net (code "102") (name "unconnected-(U6-P14-PadD4)") (class "Default")
      (node (ref "U6") (pin "D4") (pinfunction "P14_D4") (pintype "bidirectional"))
    )
    (net (code "103") (name "unconnected-(U6-P15-PadC4)") (class "Default")
      (node (ref "U6") (pin "C4") (pinfunction "P15_C4") (pintype "bidirectional"))
    )
    (net (code "104") (name "unconnected-(U6-P16-PadD3)") (class "Default")
      (node (ref "U6") (pin "D3") (pinfunction "P16_D3") (pintype "bidirectional"))
    )
    (net (code "105") (name "unconnected-(U6-P17-PadC3)") (class "Default")
      (node (ref "U6") (pin "C3") (pinfunction "P17_C3") (pintype "bidirectional"))
    )
    (net (code "106") (name "unconnected-(U6-P018-Pad12)") (class "Default")
      (node (ref "U6") (pin "12") (pinfunction "P018_12") (pintype "bidirectional"))
    )
    (net (code "107") (name "unconnected-(U6-P19-PadD2)") (class "Default")
      (node (ref "U6") (pin "D2") (pinfunction "P19_D2") (pintype "bidirectional"))
    )
    (net (code "108") (name "unconnected-(U6-P020{slash}LED-Pad13)") (class "Default")
      (node (ref "U6") (pin "13") (pinfunction "P020/LED_13") (pintype "bidirectional"))
    )
    (net (code "109") (name "unconnected-(U6-P021{slash}RESET-Pad14)") (class "Default")
      (node (ref "U6") (pin "14") (pinfunction "P021/RESET_14") (pintype "bidirectional"))
    )
    (net (code "110") (name "unconnected-(U6-P22-PadC2)") (class "Default")
      (node (ref "U6") (pin "C2") (pinfunction "P22_C2") (pintype "bidirectional"))
    )
    (net (code "111") (name "unconnected-(U6-P23-PadD1)") (class "Default")
      (node (ref "U6") (pin "D1") (pinfunction "P23_D1") (pintype "bidirectional"))
    )
    (net (code "112") (name "unconnected-(U6-P24-PadC1)") (class "Default")
      (node (ref "U6") (pin "C1") (pinfunction "P24_C1") (pintype "bidirectional"))
    )
    (net (code "113") (name "unconnected-(U6-P25-PadB1)") (class "Default")
      (node (ref "U6") (pin "B1") (pinfunction "P25_B1") (pintype "bidirectional"))
    )
    (net (code "114") (name "unconnected-(U6-P026{slash}SDA-Pad1)") (class "Default")
      (node (ref "U6") (pin "1") (pinfunction "P026/SDA_1") (pintype "bidirectional"))
    )
    (net (code "115") (name "unconnected-(U6-P027{slash}SCL-Pad2)") (class "Default")
      (node (ref "U6") (pin "2") (pinfunction "P027/SCL_2") (pintype "bidirectional"))
    )
    (net (code "116") (name "unconnected-(U6-P28-PadA1)") (class "Default")
      (node (ref "U6") (pin "A1") (pinfunction "P28_A1") (pintype "bidirectional"))
    )
    (net (code "117") (name "unconnected-(U6-P29-PadA2)") (class "Default")
      (node (ref "U6") (pin "A2") (pinfunction "P29_A2") (pintype "bidirectional"))
    )
    (net (code "118") (name "unconnected-(U6-P30-PadB2)") (class "Default")
      (node (ref "U6") (pin "B2") (pinfunction "P30_B2") (pintype "bidirectional"))
    )
    (net (code "119") (name "unconnected-(U6-P31-PadB4)") (class "Default")
      (node (ref "U6") (pin "B4") (pinfunction "P31_B4") (pintype "bidirectional"))
    )
    (net (code "120") (name "unconnected-(U6-SWCLK-Pad15)") (class "Default")
      (node (ref "U6") (pin "15") (pinfunction "SWCLK_15") (pintype "bidirectional"))
    )
    (net (code "121") (name "unconnected-(U6-SWDIO-Pad16)") (class "Default")
      (node (ref "U6") (pin "16") (pinfunction "SWDIO_16") (pintype "bidirectional"))
    )
  )
)
